# PWR_SEPIC_P12V_N12V.net
KiCad netlist of a schematic drawn in Altium Designer
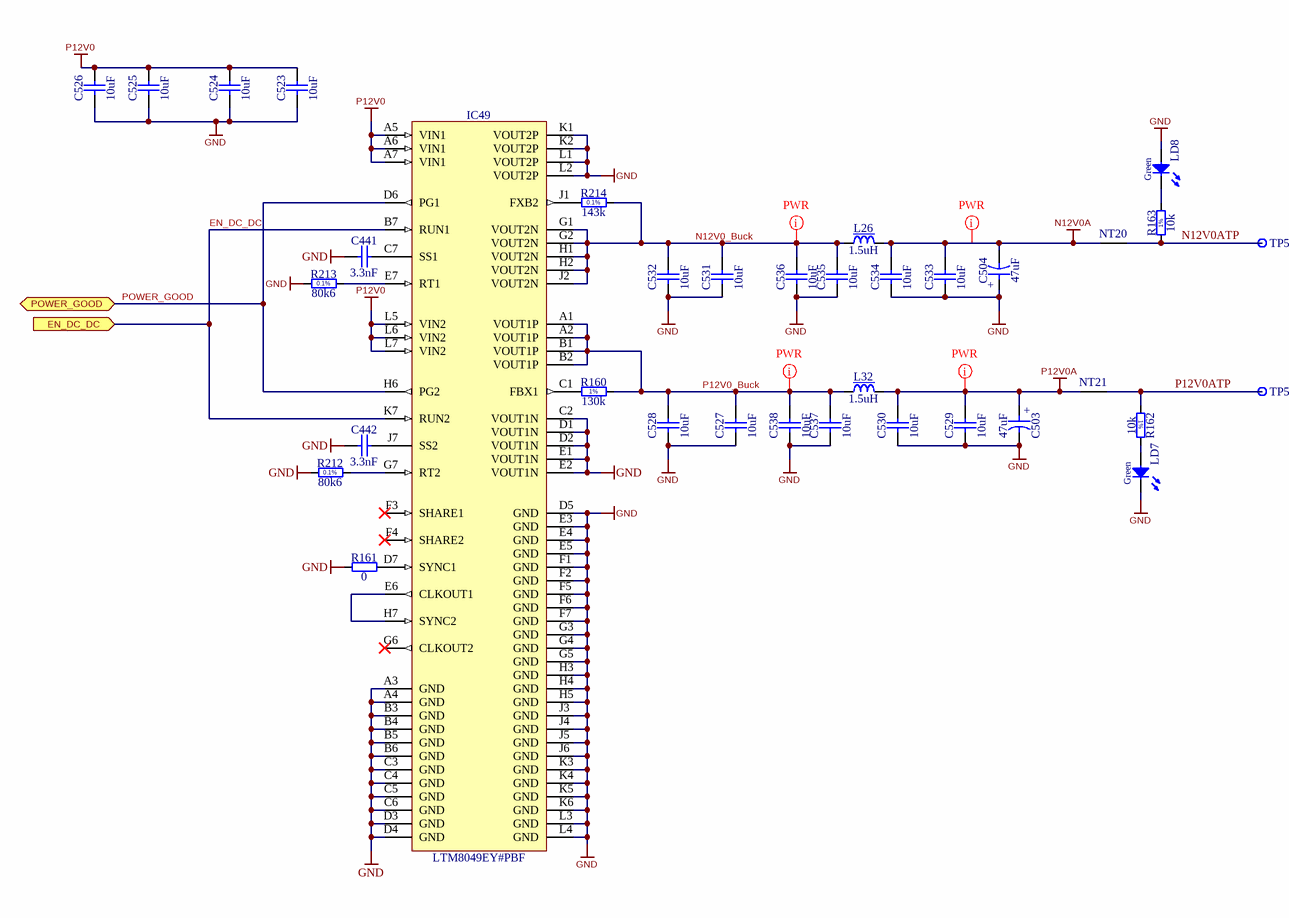
[diagram p0: PWR_SEPIC_P12V_N12V.SchDoc]

(export (version "E")
  (design (tool "Eeschema 10.0.6"))
  (components
    (comp (ref "C441")
      (value "3.3nF")
      (footprint "CAPC1005X55N")
      (description "Non-polarised capacitor")
      (fields
        (field (name "MANUFACTURER PART NUMBER") "CC0402_3.3NF_50V_10%_X7R")
        (field (name "MANUFACTURER") "GENERIC")
        (field (name "AUTHOR") "CERN DEM JLC")
      )
      (libsource (lib "Capacitors") (part "Capacitor - non polarized"))
    )
    (comp (ref "C442")
      (value "3.3nF")
      (footprint "CAPC1005X55N")
      (description "Non-polarised capacitor")
      (fields
        (field (name "MANUFACTURER PART NUMBER") "CC0402_3.3NF_50V_10%_X7R")
        (field (name "MANUFACTURER") "GENERIC")
        (field (name "AUTHOR") "CERN DEM JLC")
      )
      (libsource (lib "Capacitors") (part "Capacitor - non polarized"))
    )
    (comp (ref "C503")
      (value "47uF")
      (footprint "CAPMP6032X280N")
      (description "Polarised capacitor")
      (fields
        (field (name "MANUFACTURER PART NUMBER") "CTE6032-28_47UF_16V_10%_LESR0350")
        (field (name "MANUFACTURER") "GENERIC")
        (field (name "AUTHOR") "CERN DEM JLC")
      )
      (libsource (lib "Capacitors") (part "Capacitor - polarized"))
    )
    (comp (ref "C504")
      (value "47uF")
      (footprint "CAPMP6032X280N")
      (description "Polarised capacitor")
      (fields
        (field (name "MANUFACTURER PART NUMBER") "CTE6032-28_47UF_16V_10%_LESR0350")
        (field (name "MANUFACTURER") "GENERIC")
        (field (name "AUTHOR") "CERN DEM JLC")
      )
      (libsource (lib "Capacitors") (part "Capacitor - polarized"))
    )
    (comp (ref "C523")
      (value "10uF")
      (footprint "CAPC2012X95N")
      (description "Non-polarised capacitor")
      (fields
        (field (name "MANUFACTURER PART NUMBER") "CC0805_10UF_25V_10%_X5R")
        (field (name "MANUFACTURER") "GENERIC")
        (field (name "AUTHOR") "CERN DEM JLC")
      )
      (libsource (lib "Capacitors") (part "Capacitor - non polarized"))
    )
    (comp (ref "C524")
      (value "10uF")
      (footprint "CAPC2012X95N")
      (description "Non-polarised capacitor")
      (fields
        (field (name "MANUFACTURER PART NUMBER") "CC0805_10UF_25V_10%_X5R")
        (field (name "MANUFACTURER") "GENERIC")
        (field (name "AUTHOR") "CERN DEM JLC")
      )
      (libsource (lib "Capacitors") (part "Capacitor - non polarized"))
    )
    (comp (ref "C525")
      (value "10uF")
      (footprint "CAPC2012X95N")
      (description "Non-polarised capacitor")
      (fields
        (field (name "MANUFACTURER PART NUMBER") "CC0805_10UF_25V_10%_X5R")
        (field (name "MANUFACTURER") "GENERIC")
        (field (name "AUTHOR") "CERN DEM JLC")
      )
      (libsource (lib "Capacitors") (part "Capacitor - non polarized"))
    )
    (comp (ref "C526")
      (value "10uF")
      (footprint "CAPC2012X95N")
      (description "Non-polarised capacitor")
      (fields
        (field (name "MANUFACTURER PART NUMBER") "CC0805_10UF_25V_10%_X5R")
        (field (name "MANUFACTURER") "GENERIC")
        (field (name "AUTHOR") "CERN DEM JLC")
      )
      (libsource (lib "Capacitors") (part "Capacitor - non polarized"))
    )
    (comp (ref "C527")
      (value "10uF")
      (footprint "CAPC2012X95N")
      (description "Non-polarised capacitor")
      (fields
        (field (name "MANUFACTURER PART NUMBER") "CC0805_10UF_25V_10%_X5R")
        (field (name "MANUFACTURER") "GENERIC")
        (field (name "AUTHOR") "CERN DEM JLC")
      )
      (libsource (lib "Capacitors") (part "Capacitor - non polarized"))
    )
    (comp (ref "C528")
      (value "10uF")
      (footprint "CAPC2012X95N")
      (description "Non-polarised capacitor")
      (fields
        (field (name "MANUFACTURER PART NUMBER") "CC0805_10UF_25V_10%_X5R")
        (field (name "MANUFACTURER") "GENERIC")
        (field (name "AUTHOR") "CERN DEM JLC")
      )
      (libsource (lib "Capacitors") (part "Capacitor - non polarized"))
    )
    (comp (ref "C529")
      (value "10uF")
      (footprint "CAPC2012X95N")
      (description "Non-polarised capacitor")
      (fields
        (field (name "MANUFACTURER PART NUMBER") "CC0805_10UF_25V_10%_X5R")
        (field (name "MANUFACTURER") "GENERIC")
        (field (name "AUTHOR") "CERN DEM JLC")
      )
      (libsource (lib "Capacitors") (part "Capacitor - non polarized"))
    )
    (comp (ref "C530")
      (value "10uF")
      (footprint "CAPC2012X95N")
      (description "Non-polarised capacitor")
      (fields
        (field (name "MANUFACTURER PART NUMBER") "CC0805_10UF_25V_10%_X5R")
        (field (name "MANUFACTURER") "GENERIC")
        (field (name "AUTHOR") "CERN DEM JLC")
      )
      (libsource (lib "Capacitors") (part "Capacitor - non polarized"))
    )
    (comp (ref "C531")
      (value "10uF")
      (footprint "CAPC2012X95N")
      (description "Non-polarised capacitor")
      (fields
        (field (name "MANUFACTURER PART NUMBER") "CC0805_10UF_25V_10%_X5R")
        (field (name "MANUFACTURER") "GENERIC")
        (field (name "AUTHOR") "CERN DEM JLC")
      )
      (libsource (lib "Capacitors") (part "Capacitor - non polarized"))
    )
    (comp (ref "C532")
      (value "10uF")
      (footprint "CAPC2012X95N")
      (description "Non-polarised capacitor")
      (fields
        (field (name "MANUFACTURER PART NUMBER") "CC0805_10UF_25V_10%_X5R")
        (field (name "MANUFACTURER") "GENERIC")
        (field (name "AUTHOR") "CERN DEM JLC")
      )
      (libsource (lib "Capacitors") (part "Capacitor - non polarized"))
    )
    (comp (ref "C533")
      (value "10uF")
      (footprint "CAPC2012X95N")
      (description "Non-polarised capacitor")
      (fields
        (field (name "MANUFACTURER PART NUMBER") "CC0805_10UF_25V_10%_X5R")
        (field (name "MANUFACTURER") "GENERIC")
        (field (name "AUTHOR") "CERN DEM JLC")
      )
      (libsource (lib "Capacitors") (part "Capacitor - non polarized"))
    )
    (comp (ref "C534")
      (value "10uF")
      (footprint "CAPC2012X95N")
      (description "Non-polarised capacitor")
      (fields
        (field (name "MANUFACTURER PART NUMBER") "CC0805_10UF_25V_10%_X5R")
        (field (name "MANUFACTURER") "GENERIC")
        (field (name "AUTHOR") "CERN DEM JLC")
      )
      (libsource (lib "Capacitors") (part "Capacitor - non polarized"))
    )
    (comp (ref "C535")
      (value "10uF")
      (footprint "CAPC2012X95N")
      (description "Non-polarised capacitor")
      (fields
        (field (name "MANUFACTURER PART NUMBER") "CC0805_10UF_25V_10%_X5R")
        (field (name "MANUFACTURER") "GENERIC")
        (field (name "AUTHOR") "CERN DEM JLC")
      )
      (libsource (lib "Capacitors") (part "Capacitor - non polarized"))
    )
    (comp (ref "C536")
      (value "10uF")
      (footprint "CAPC2012X95N")
      (description "Non-polarised capacitor")
      (fields
        (field (name "MANUFACTURER PART NUMBER") "CC0805_10UF_25V_10%_X5R")
        (field (name "MANUFACTURER") "GENERIC")
        (field (name "AUTHOR") "CERN DEM JLC")
      )
      (libsource (lib "Capacitors") (part "Capacitor - non polarized"))
    )
    (comp (ref "C537")
      (value "10uF")
      (footprint "CAPC2012X95N")
      (description "Non-polarised capacitor")
      (fields
        (field (name "MANUFACTURER PART NUMBER") "CC0805_10UF_25V_10%_X5R")
        (field (name "MANUFACTURER") "GENERIC")
        (field (name "AUTHOR") "CERN DEM JLC")
      )
      (libsource (lib "Capacitors") (part "Capacitor - non polarized"))
    )
    (comp (ref "C538")
      (value "10uF")
      (footprint "CAPC2012X95N")
      (description "Non-polarised capacitor")
      (fields
        (field (name "MANUFACTURER PART NUMBER") "CC0805_10UF_25V_10%_X5R")
        (field (name "MANUFACTURER") "GENERIC")
        (field (name "AUTHOR") "CERN DEM JLC")
      )
      (libsource (lib "Capacitors") (part "Capacitor - non polarized"))
    )
    (comp (ref "IC49")
      (value "LTM8049EY#PBF")
      (footprint "BGA77C127P7X11_900X1500X262")
      (description "Dual SEPIC or Inverting uModule DC/DC Converter")
      (fields (field (name "MANUFACTURER") "LINEAR TECHNOLOGY") (field (name "AUTHOR") "CERN DEM JLC"))
      (libsource (lib "ICs And Semiconductors") (part "LTM8049"))
    )
    (comp (ref "L26")
      (value "1.5uH")
      (footprint "IND_TDK_SPM6530")
      (description "Inductor With Core")
      (fields
        (field (name "MANUFACTURER PART NUMBER") "SPM6530T-1R5M100")
        (field (name "MANUFACTURER") "TDK")
        (field (name "AUTHOR") "CERN DEM MR")
      )
      (libsource (lib "Inductors & Transformers") (part "Inductor With Magnetic core"))
    )
    (comp (ref "L32")
      (value "1.5uH")
      (footprint "IND_TDK_SPM6530")
      (description "Inductor With Core")
      (fields
        (field (name "MANUFACTURER PART NUMBER") "SPM6530T-1R5M100")
        (field (name "MANUFACTURER") "TDK")
        (field (name "AUTHOR") "CERN DEM MR")
      )
      (libsource (lib "Inductors & Transformers") (part "Inductor With Magnetic core"))
    )
    (comp (ref "LD7")
      (value "Green")
      (footprint "LED_KINGBRIGHT_KPH-1608CGCK")
      (description "LED Green 1C 2A")
      (fields
        (field (name "MANUFACTURER PART NUMBER") "KPH-1608CGCK")
        (field (name "MANUFACTURER") "KINGBRIGHT")
        (field (name "AUTHOR") "CERN DEM JLC")
      )
      (libsource (lib "ICs And Semiconductors") (part "LED Green 1C 2A"))
    )
    (comp (ref "LD8")
      (value "Green")
      (footprint "LED_KINGBRIGHT_KPH-1608CGCK")
      (description "LED Green 1C 2A")
      (fields
        (field (name "MANUFACTURER PART NUMBER") "KPH-1608CGCK")
        (field (name "MANUFACTURER") "KINGBRIGHT")
        (field (name "AUTHOR") "CERN DEM JLC")
      )
      (libsource (lib "ICs And Semiconductors") (part "LED Green 1C 2A"))
    )
    (comp (ref "NT20")
      (value "Net Tie")
      (footprint "Net Tie")
      (fields (field (name "AUTHOR") "CERN DEM JLC"))
      (libsource (lib "Eletro-mechanical") (part "Net Tie"))
    )
    (comp (ref "NT21")
      (value "Net Tie")
      (footprint "Net Tie")
      (fields (field (name "AUTHOR") "CERN DEM JLC"))
      (libsource (lib "Eletro-mechanical") (part "Net Tie"))
    )
    (comp (ref "R160")
      (value "130k")
      (footprint "RESC1005X40N")
      (description "Resistor - 1%")
      (fields
        (field (name "MANUFACTURER PART NUMBER") "R0402_130K_1%_0.0625W_100PPM")
        (field (name "MANUFACTURER") "GENERIC")
        (field (name "AUTHOR") "CERN DEM JLC")
      )
      (libsource (lib "Resistors") (part "Resistor - 1%"))
    )
    (comp (ref "R161")
      (value "0")
      (footprint "RESC1005X40N")
      (description "Resistor")
      (fields
        (field (name "MANUFACTURER PART NUMBER") "R0402_0R_JUMPER")
        (field (name "MANUFACTURER") "GENERIC")
        (field (name "AUTHOR") "CERN DEM JLC")
      )
      (libsource (lib "Resistors") (part "Resistor"))
    )
    (comp (ref "R162")
      (value "10k")
      (footprint "RESC1005X40N")
      (description "Resistor - 1%")
      (fields
        (field (name "MANUFACTURER PART NUMBER") "R0402_10K_1%_0.0625W_100PPM")
        (field (name "MANUFACTURER") "GENERIC")
        (field (name "AUTHOR") "CERN DEM JLC")
      )
      (libsource (lib "Resistors") (part "Resistor - 1%"))
    )
    (comp (ref "R163")
      (value "10k")
      (footprint "RESC1005X40N")
      (description "Resistor - 1%")
      (fields
        (field (name "MANUFACTURER PART NUMBER") "R0402_10K_1%_0.0625W_100PPM")
        (field (name "MANUFACTURER") "GENERIC")
        (field (name "AUTHOR") "CERN DEM JLC")
      )
      (libsource (lib "Resistors") (part "Resistor - 1%"))
    )
    (comp (ref "R212")
      (value "80k6")
      (footprint "RESC1608X55N")
      (description "Resistor - 0.1%")
      (fields
        (field (name "MANUFACTURER PART NUMBER") "R0603_80K6_0.1%_0.063W_10PPM")
        (field (name "MANUFACTURER") "GENERIC")
        (field (name "AUTHOR") "CERN DEM JLC")
      )
      (libsource (lib "Resistors") (part "Resistor - 0.1%"))
    )
    (comp (ref "R213")
      (value "80k6")
      (footprint "RESC1608X55N")
      (description "Resistor - 0.1%")
      (fields
        (field (name "MANUFACTURER PART NUMBER") "R0603_80K6_0.1%_0.063W_10PPM")
        (field (name "MANUFACTURER") "GENERIC")
        (field (name "AUTHOR") "CERN DEM JLC")
      )
      (libsource (lib "Resistors") (part "Resistor - 0.1%"))
    )
    (comp (ref "R214")
      (value "143k")
      (footprint "RESC1608X55N")
      (description "Resistor - 0.1%")
      (fields
        (field (name "MANUFACTURER PART NUMBER") "R0603_143K_0.1%_0.063W_10PPM")
        (field (name "MANUFACTURER") "GENERIC")
        (field (name "AUTHOR") "CERN DEM JLC")
      )
      (libsource (lib "Resistors") (part "Resistor - 0.1%"))
    )
    (comp (ref "TP55")
      (value "Test Point")
      (footprint "TPS127")
      (fields (field (name "PART NUMBER") "SMD_PAD_1.27X1.27MM") (field (name "AUTHOR") "CERN DEM JLC"))
      (libsource (lib "Eletro-mechanical") (part "Test Point"))
    )
    (comp (ref "TP56")
      (value "Test Point")
      (footprint "TPS127")
      (fields (field (name "PART NUMBER") "SMD_PAD_1.27X1.27MM") (field (name "AUTHOR") "CERN DEM JLC"))
      (libsource (lib "Eletro-mechanical") (part "Test Point"))
    )
  )
  (nets
    (net (code "1") (name "/EN_DC_DC") (class "Default")
      (node (ref "IC49") (pin "B7") (pinfunction "RUN1_B7") (pintype "input"))
      (node (ref "IC49") (pin "K7") (pinfunction "RUN2_K7") (pintype "input"))
    )
    (net (code "2") (name "/N12V0ATP") (class "Default")
      (node (ref "NT20") (pin "2") (pinfunction "2_2") (pintype "bidirectional"))
      (node (ref "R163") (pin "1") (pinfunction "1_1") (pintype "passive"))
      (node (ref "TP55") (pin "1") (pinfunction "1_1") (pintype "bidirectional"))
    )
    (net (code "3") (name "/N12V0_Buck") (class "Default")
      (node (ref "C531") (pin "2") (pinfunction "2_2") (pintype "passive"))
      (node (ref "C532") (pin "2") (pinfunction "2_2") (pintype "passive"))
      (node (ref "C535") (pin "2") (pinfunction "2_2") (pintype "passive"))
      (node (ref "C536") (pin "2") (pinfunction "2_2") (pintype "passive"))
      (node (ref "IC49") (pin "G1") (pinfunction "VOUT2N_G1") (pintype "power_in"))
      (node (ref "IC49") (pin "G2") (pinfunction "VOUT2N_G2") (pintype "power_in"))
      (node (ref "IC49") (pin "H1") (pinfunction "VOUT2N_H1") (pintype "power_in"))
      (node (ref "IC49") (pin "H2") (pinfunction "VOUT2N_H2") (pintype "power_in"))
      (node (ref "IC49") (pin "J2") (pinfunction "VOUT2N_J2") (pintype "power_in"))
      (node (ref "L26") (pin "1") (pinfunction "1_1") (pintype "passive"))
      (node (ref "R214") (pin "2") (pinfunction "2_2") (pintype "passive"))
    )
    (net (code "4") (name "/P12V0ATP") (class "Default")
      (node (ref "NT21") (pin "2") (pinfunction "2_2") (pintype "bidirectional"))
      (node (ref "R162") (pin "1") (pinfunction "1_1") (pintype "passive"))
      (node (ref "TP56") (pin "1") (pinfunction "1_1") (pintype "bidirectional"))
    )
    (net (code "5") (name "/P12V0_Buck") (class "Default")
      (node (ref "C527") (pin "2") (pinfunction "2_2") (pintype "passive"))
      (node (ref "C528") (pin "2") (pinfunction "2_2") (pintype "passive"))
      (node (ref "C537") (pin "2") (pinfunction "2_2") (pintype "passive"))
      (node (ref "C538") (pin "2") (pinfunction "2_2") (pintype "passive"))
      (node (ref "IC49") (pin "A1") (pinfunction "VOUT1P_A1") (pintype "power_in"))
      (node (ref "IC49") (pin "A2") (pinfunction "VOUT1P_A2") (pintype "power_in"))
      (node (ref "IC49") (pin "B1") (pinfunction "VOUT1P_B1") (pintype "power_in"))
      (node (ref "IC49") (pin "B2") (pinfunction "VOUT1P_B2") (pintype "power_in"))
      (node (ref "L32") (pin "1") (pinfunction "1_1") (pintype "passive"))
      (node (ref "R160") (pin "2") (pinfunction "2_2") (pintype "passive"))
    )
    (net (code "6") (name "/POWER_GOOD") (class "Default")
      (node (ref "IC49") (pin "D6") (pinfunction "PG1_D6") (pintype "output"))
      (node (ref "IC49") (pin "H6") (pinfunction "PG2_H6") (pintype "output"))
    )
    (net (code "7") (name "GND") (class "Default")
      (node (ref "C441") (pin "1") (pinfunction "1_1") (pintype "passive"))
      (node (ref "C442") (pin "1") (pinfunction "1_1") (pintype "passive"))
      (node (ref "C503") (pin "2") (pinfunction "2_2") (pintype "passive"))
      (node (ref "C504") (pin "1") (pinfunction "1_1") (pintype "passive"))
      (node (ref "C523") (pin "1") (pinfunction "1_1") (pintype "passive"))
      (node (ref "C524") (pin "1") (pinfunction "1_1") (pintype "passive"))
      (node (ref "C525") (pin "1") (pinfunction "1_1") (pintype "passive"))
      (node (ref "C526") (pin "1") (pinfunction "1_1") (pintype "passive"))
      (node (ref "C527") (pin "1") (pinfunction "1_1") (pintype "passive"))
      (node (ref "C528") (pin "1") (pinfunction "1_1") (pintype "passive"))
      (node (ref "C529") (pin "1") (pinfunction "1_1") (pintype "passive"))
      (node (ref "C530") (pin "1") (pinfunction "1_1") (pintype "passive"))
      (node (ref "C531") (pin "1") (pinfunction "1_1") (pintype "passive"))
      (node (ref "C532") (pin "1") (pinfunction "1_1") (pintype "passive"))
      (node (ref "C533") (pin "1") (pinfunction "1_1") (pintype "passive"))
      (node (ref "C534") (pin "1") (pinfunction "1_1") (pintype "passive"))
      (node (ref "C535") (pin "1") (pinfunction "1_1") (pintype "passive"))
      (node (ref "C536") (pin "1") (pinfunction "1_1") (pintype "passive"))
      (node (ref "C537") (pin "1") (pinfunction "1_1") (pintype "passive"))
      (node (ref "C538") (pin "1") (pinfunction "1_1") (pintype "passive"))
      (node (ref "IC49") (pin "A3") (pinfunction "GND_A3") (pintype "power_in"))
      (node (ref "IC49") (pin "A4") (pinfunction "GND_A4") (pintype "power_in"))
      (node (ref "IC49") (pin "B3") (pinfunction "GND_B3") (pintype "power_in"))
      (node (ref "IC49") (pin "B4") (pinfunction "GND_B4") (pintype "power_in"))
      (node (ref "IC49") (pin "B5") (pinfunction "GND_B5") (pintype "power_in"))
      (node (ref "IC49") (pin "B6") (pinfunction "GND_B6") (pintype "power_in"))
      (node (ref "IC49") (pin "C2") (pinfunction "VOUT1N_C2") (pintype "power_in"))
      (node (ref "IC49") (pin "C3") (pinfunction "GND_C3") (pintype "power_in"))
      (node (ref "IC49") (pin "C4") (pinfunction "GND_C4") (pintype "power_in"))
      (node (ref "IC49") (pin "C5") (pinfunction "GND_C5") (pintype "power_in"))
      (node (ref "IC49") (pin "C6") (pinfunction "GND_C6") (pintype "power_in"))
      (node (ref "IC49") (pin "D1") (pinfunction "VOUT1N_D1") (pintype "power_in"))
      (node (ref "IC49") (pin "D2") (pinfunction "VOUT1N_D2") (pintype "power_in"))
      (node (ref "IC49") (pin "D3") (pinfunction "GND_D3") (pintype "power_in"))
      (node (ref "IC49") (pin "D4") (pinfunction "GND_D4") (pintype "power_in"))
      (node (ref "IC49") (pin "D5") (pinfunction "GND_D5") (pintype "power_in"))
      (node (ref "IC49") (pin "E1") (pinfunction "VOUT1N_E1") (pintype "power_in"))
      (node (ref "IC49") (pin "E2") (pinfunction "VOUT1N_E2") (pintype "power_in"))
      (node (ref "IC49") (pin "E3") (pinfunction "GND_E3") (pintype "power_in"))
      (node (ref "IC49") (pin "E4") (pinfunction "GND_E4") (pintype "power_in"))
      (node (ref "IC49") (pin "E5") (pinfunction "GND_E5") (pintype "power_in"))
      (node (ref "IC49") (pin "F1") (pinfunction "GND_F1") (pintype "power_in"))
      (node (ref "IC49") (pin "F2") (pinfunction "GND_F2") (pintype "power_in"))
      (node (ref "IC49") (pin "F5") (pinfunction "GND_F5") (pintype "power_in"))
      (node (ref "IC49") (pin "F6") (pinfunction "GND_F6") (pintype "power_in"))
      (node (ref "IC49") (pin "F7") (pinfunction "GND_F7") (pintype "power_in"))
      (node (ref "IC49") (pin "G3") (pinfunction "GND_G3") (pintype "power_in"))
      (node (ref "IC49") (pin "G4") (pinfunction "GND_G4") (pintype "power_in"))
      (node (ref "IC49") (pin "G5") (pinfunction "GND_G5") (pintype "power_in"))
      (node (ref "IC49") (pin "H3") (pinfunction "GND_H3") (pintype "power_in"))
      (node (ref "IC49") (pin "H4") (pinfunction "GND_H4") (pintype "power_in"))
      (node (ref "IC49") (pin "H5") (pinfunction "GND_H5") (pintype "power_in"))
      (node (ref "IC49") (pin "J3") (pinfunction "GND_J3") (pintype "power_in"))
      (node (ref "IC49") (pin "J4") (pinfunction "GND_J4") (pintype "power_in"))
      (node (ref "IC49") (pin "J5") (pinfunction "GND_J5") (pintype "power_in"))
      (node (ref "IC49") (pin "J6") (pinfunction "GND_J6") (pintype "power_in"))
      (node (ref "IC49") (pin "K1") (pinfunction "VOUT2P_K1") (pintype "power_in"))
      (node (ref "IC49") (pin "K2") (pinfunction "VOUT2P_K2") (pintype "power_in"))
      (node (ref "IC49") (pin "K3") (pinfunction "GND_K3") (pintype "power_in"))
      (node (ref "IC49") (pin "K4") (pinfunction "GND_K4") (pintype "power_in"))
      (node (ref "IC49") (pin "K5") (pinfunction "GND_K5") (pintype "power_in"))
      (node (ref "IC49") (pin "K6") (pinfunction "GND_K6") (pintype "power_in"))
      (node (ref "IC49") (pin "L1") (pinfunction "VOUT2P_L1") (pintype "power_in"))
      (node (ref "IC49") (pin "L2") (pinfunction "VOUT2P_L2") (pintype "power_in"))
      (node (ref "IC49") (pin "L3") (pinfunction "GND_L3") (pintype "power_in"))
      (node (ref "IC49") (pin "L4") (pinfunction "GND_L4") (pintype "power_in"))
      (node (ref "LD7") (pin "1") (pinfunction "C_1") (pintype "passive"))
      (node (ref "LD8") (pin "2") (pinfunction "A_2") (pintype "passive"))
      (node (ref "R161") (pin "1") (pinfunction "1_1") (pintype "passive"))
      (node (ref "R212") (pin "1") (pinfunction "1_1") (pintype "passive"))
      (node (ref "R213") (pin "1") (pinfunction "1_1") (pintype "passive"))
    )
    (net (code "8") (name "N12V0A") (class "Default")
      (node (ref "C504") (pin "2") (pinfunction "2_2") (pintype "passive"))
      (node (ref "C533") (pin "2") (pinfunction "2_2") (pintype "passive"))
      (node (ref "C534") (pin "2") (pinfunction "2_2") (pintype "passive"))
      (node (ref "L26") (pin "2") (pinfunction "2_2") (pintype "passive"))
      (node (ref "NT20") (pin "1") (pinfunction "1_1") (pintype "bidirectional"))
    )
    (net (code "9") (name "Net-(IC49-CLKOUT1)") (class "Default")
      (node (ref "IC49") (pin "E6") (pinfunction "CLKOUT1_E6") (pintype "output"))
      (node (ref "IC49") (pin "H7") (pinfunction "SYNC2_H7") (pintype "input"))
    )
    (net (code "10") (name "Net-(IC49-FBX1)") (class "Default")
      (node (ref "IC49") (pin "C1") (pinfunction "FBX1_C1") (pintype "output"))
      (node (ref "R160") (pin "1") (pinfunction "1_1") (pintype "passive"))
    )
    (net (code "11") (name "Net-(IC49-FXB2)") (class "Default")
      (node (ref "IC49") (pin "J1") (pinfunction "FXB2_J1") (pintype "output"))
      (node (ref "R214") (pin "1") (pinfunction "1_1") (pintype "passive"))
    )
    (net (code "12") (name "Net-(IC49-RT1)") (class "Default")
      (node (ref "IC49") (pin "E7") (pinfunction "RT1_E7") (pintype "input"))
      (node (ref "R213") (pin "2") (pinfunction "2_2") (pintype "passive"))
    )
    (net (code "13") (name "Net-(IC49-RT2)") (class "Default")
      (node (ref "IC49") (pin "G7") (pinfunction "RT2_G7") (pintype "input"))
      (node (ref "R212") (pin "2") (pinfunction "2_2") (pintype "passive"))
    )
    (net (code "14") (name "Net-(IC49-SS1)") (class "Default")
      (node (ref "C441") (pin "2") (pinfunction "2_2") (pintype "passive"))
      (node (ref "IC49") (pin "C7") (pinfunction "SS1_C7") (pintype "passive"))
    )
    (net (code "15") (name "Net-(IC49-SS2)") (class "Default")
      (node (ref "C442") (pin "2") (pinfunction "2_2") (pintype "passive"))
      (node (ref "IC49") (pin "J7") (pinfunction "SS2_J7") (pintype "passive"))
    )
    (net (code "16") (name "Net-(IC49-SYNC1)") (class "Default")
      (node (ref "IC49") (pin "D7") (pinfunction "SYNC1_D7") (pintype "input"))
      (node (ref "R161") (pin "2") (pinfunction "2_2") (pintype "passive"))
    )
    (net (code "17") (name "Net-(LD7-A)") (class "Default")
      (node (ref "LD7") (pin "2") (pinfunction "A_2") (pintype "passive"))
      (node (ref "R162") (pin "2") (pinfunction "2_2") (pintype "passive"))
    )
    (net (code "18") (name "Net-(LD8-C)") (class "Default")
      (node (ref "LD8") (pin "1") (pinfunction "C_1") (pintype "passive"))
      (node (ref "R163") (pin "2") (pinfunction "2_2") (pintype "passive"))
    )
    (net (code "19") (name "P12V0") (class "Default")
      (node (ref "C523") (pin "2") (pinfunction "2_2") (pintype "passive"))
      (node (ref "C524") (pin "2") (pinfunction "2_2") (pintype "passive"))
      (node (ref "C525") (pin "2") (pinfunction "2_2") (pintype "passive"))
      (node (ref "C526") (pin "2") (pinfunction "2_2") (pintype "passive"))
      (node (ref "IC49") (pin "A5") (pinfunction "VIN1_A5") (pintype "input"))
      (node (ref "IC49") (pin "A6") (pinfunction "VIN1_A6") (pintype "input"))
      (node (ref "IC49") (pin "A7") (pinfunction "VIN1_A7") (pintype "input"))
      (node (ref "IC49") (pin "L5") (pinfunction "VIN2_L5") (pintype "input"))
      (node (ref "IC49") (pin "L6") (pinfunction "VIN2_L6") (pintype "input"))
      (node (ref "IC49") (pin "L7") (pinfunction "VIN2_L7") (pintype "input"))
    )
    (net (code "20") (name "P12V0A") (class "Default")
      (node (ref "C503") (pin "1") (pinfunction "1_1") (pintype "passive"))
      (node (ref "C529") (pin "2") (pinfunction "2_2") (pintype "passive"))
      (node (ref "C530") (pin "2") (pinfunction "2_2") (pintype "passive"))
      (node (ref "L32") (pin "2") (pinfunction "2_2") (pintype "passive"))
      (node (ref "NT21") (pin "1") (pinfunction "1_1") (pintype "bidirectional"))
    )
    (net (code "21") (name "unconnected-(IC49-CLKOUT2-PadG6)") (class "Default")
      (node (ref "IC49") (pin "G6") (pinfunction "CLKOUT2_G6") (pintype "output+no_connect"))
    )
    (net (code "22") (name "unconnected-(IC49-SHARE1-PadF3)") (class "Default")
      (node (ref "IC49") (pin "F3") (pinfunction "SHARE1_F3") (pintype "input+no_connect"))
    )
    (net (code "23") (name "unconnected-(IC49-SHARE2-PadF4)") (class "Default")
      (node (ref "IC49") (pin "F4") (pinfunction "SHARE2_F4") (pintype "input+no_connect"))
    )
  )
)
